# spi_iic_uart.net
KiCad netlist of a schematic drawn in Altium Designer
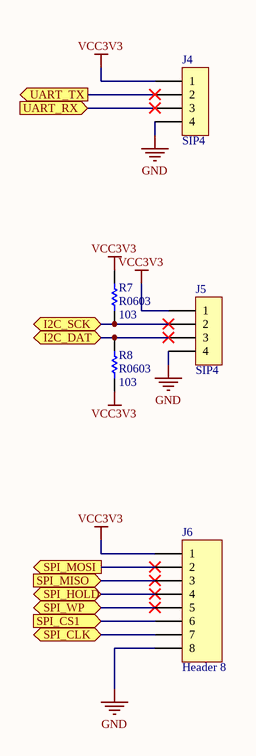
[diagram p0: spi_iic_uart.SchDoc]

(export (version "E")
  (design (tool "Eeschema 10.0.6"))
  (components
    (comp (ref "J4")
      (value "SIP4")
      (footprint "SIP4-2.54")
      (description "jointbar")
      (libsource (lib "schumyhao's_Device") (part "SIP4"))
    )
    (comp (ref "J5")
      (value "SIP4")
      (footprint "SIP4-2.54")
      (description "jointbar")
      (libsource (lib "schumyhao's_Device") (part "SIP4"))
    )
    (comp (ref "J6")
      (value "Header 8")
      (footprint "HDR1X8")
      (description "Header, 8-Pin")
      (fields (field (name "PUBLISHER") "Altium Limited"))
      (libsource (lib "Miscellaneous Connectors") (part "Header 8"))
    )
    (comp (ref "R7")
      (value "R0603")
      (footprint "R0603N")
      (description "Semiconductor Resistor")
      (fields (field (name "ALTIUM_VALUE") "103"))
      (libsource (lib "schumyhao's_Device") (part "Res Semi"))
    )
    (comp (ref "R8")
      (value "R0603")
      (footprint "R0603N")
      (description "Semiconductor Resistor")
      (fields (field (name "ALTIUM_VALUE") "103"))
      (libsource (lib "schumyhao's_Device") (part "Res Semi"))
    )
  )
  (nets
    (net (code "1") (name "/I2C_DAT") (class "Default")
      (node (ref "J5") (pin "3") (pinfunction "3_3") (pintype "passive"))
      (node (ref "R8") (pin "2") (pinfunction "2_2") (pintype "passive"))
    )
    (net (code "2") (name "/I2C_SCK") (class "Default")
      (node (ref "J5") (pin "2") (pinfunction "2_2") (pintype "passive"))
      (node (ref "R7") (pin "1") (pinfunction "1_1") (pintype "passive"))
    )
    (net (code "3") (name "/SPI_CLK") (class "Default")
      (node (ref "J6") (pin "7") (pinfunction "7_7") (pintype "passive"))
    )
    (net (code "4") (name "/SPI_CS1") (class "Default")
      (node (ref "J6") (pin "6") (pinfunction "6_6") (pintype "passive"))
    )
    (net (code "5") (name "/SPI_HOLD") (class "Default")
      (node (ref "J6") (pin "4") (pinfunction "4_4") (pintype "passive+no_connect"))
    )
    (net (code "6") (name "/SPI_MISO") (class "Default")
      (node (ref "J6") (pin "3") (pinfunction "3_3") (pintype "passive+no_connect"))
    )
    (net (code "7") (name "/SPI_MOSI") (class "Default")
      (node (ref "J6") (pin "2") (pinfunction "2_2") (pintype "passive+no_connect"))
    )
    (net (code "8") (name "/SPI_WP") (class "Default")
      (node (ref "J6") (pin "5") (pinfunction "5_5") (pintype "passive+no_connect"))
    )
    (net (code "9") (name "/UART_RX") (class "Default")
      (node (ref "J4") (pin "3") (pinfunction "3_3") (pintype "passive+no_connect"))
    )
    (net (code "10") (name "/UART_TX") (class "Default")
      (node (ref "J4") (pin "2") (pinfunction "2_2") (pintype "passive+no_connect"))
    )
    (net (code "11") (name "GND") (class "Default")
      (node (ref "J4") (pin "4") (pinfunction "4_4") (pintype "passive"))
      (node (ref "J5") (pin "4") (pinfunction "4_4") (pintype "passive"))
      (node (ref "J6") (pin "8") (pinfunction "8_8") (pintype "passive"))
    )
    (net (code "12") (name "VCC3V3") (class "Default")
      (node (ref "J4") (pin "1") (pinfunction "1_1") (pintype "passive"))
      (node (ref "J5") (pin "1") (pinfunction "1_1") (pintype "passive"))
      (node (ref "J6") (pin "1") (pinfunction "1_1") (pintype "passive"))
      (node (ref "R7") (pin "2") (pinfunction "2_2") (pintype "passive"))
      (node (ref "R8") (pin "1") (pinfunction "1_1") (pintype "passive"))
    )
  )
)
